# WIFIBT_AP6212.net
KiCad netlist of a schematic drawn in Altium Designer
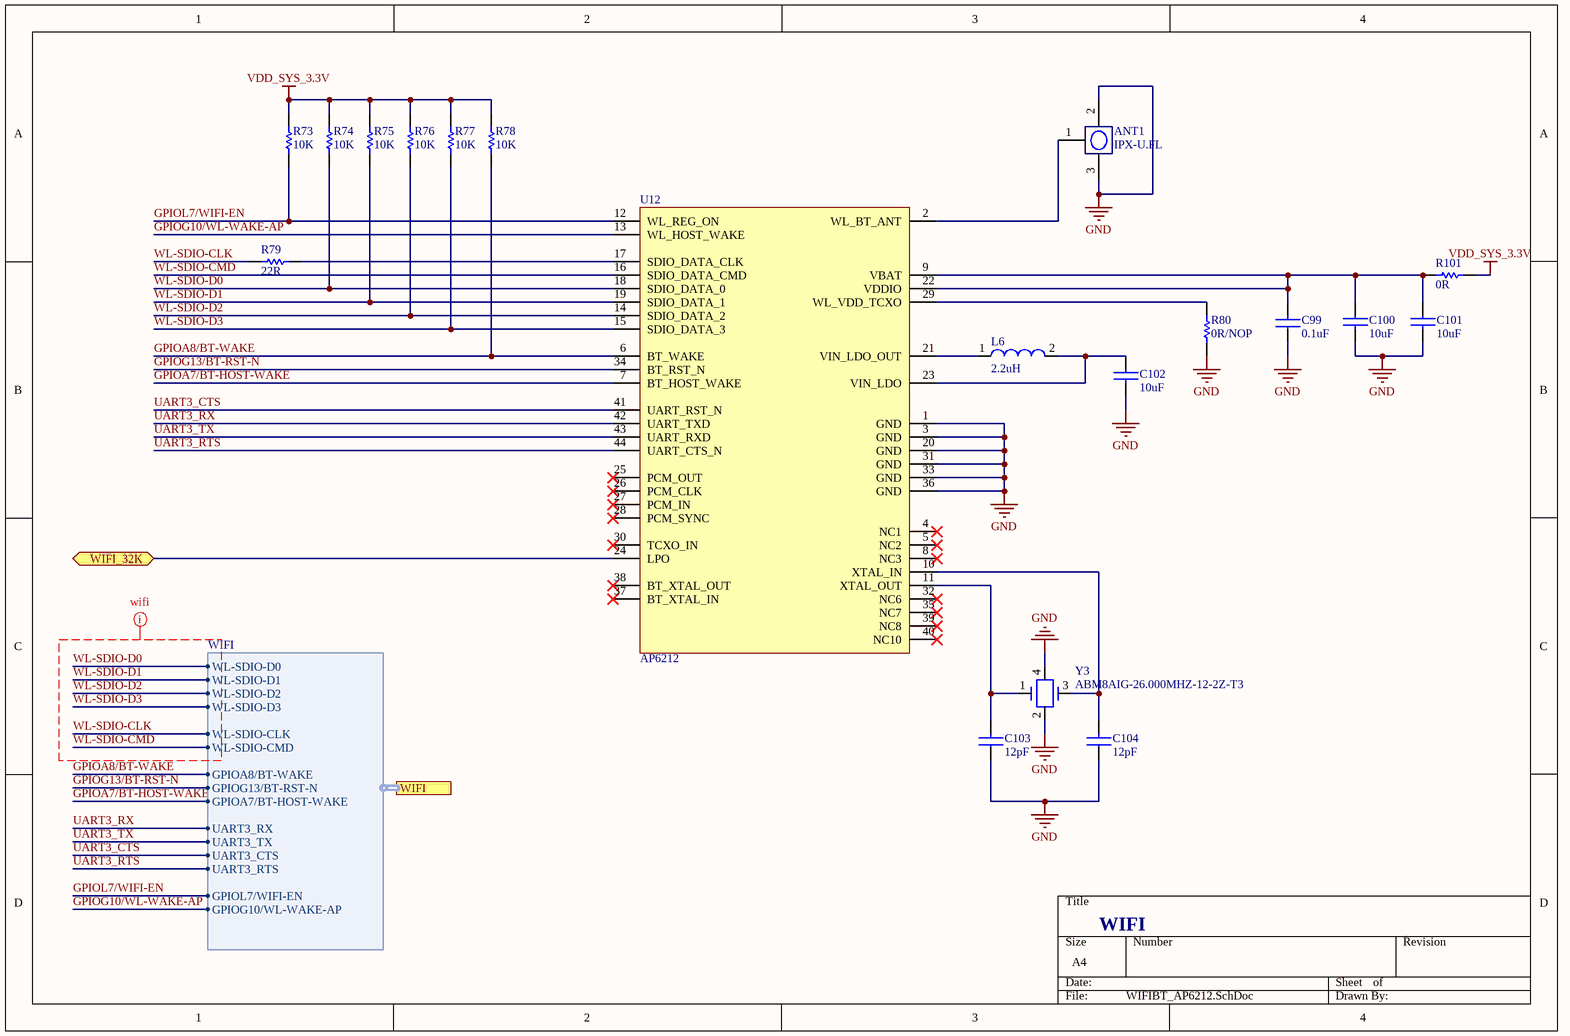
[diagram p0: WIFIBT_AP6212.SchDoc]

(export (version "E")
  (design (tool "Eeschema 10.0.6"))
  (components
    (comp (ref "ANT1") (value "IPX-U.FL") (footprint "UFL") (libsource (lib "MH") (part "ANT1")))
    (comp (ref "C99")
      (value "0.1uF")
      (footprint "C0402")
      (fields (field (name "PART NUMBER") "GCM188L81H104KA57D"))
      (libsource (lib "MH") (part "CAPC"))
    )
    (comp (ref "C100")
      (value "10uF")
      (footprint "C0603")
      (fields (field (name "PART NUMBER") "GRM188R60J106ME47D"))
      (libsource (lib "MH") (part "CAPC"))
    )
    (comp (ref "C101")
      (value "10uF")
      (footprint "C0603")
      (fields (field (name "PART NUMBER") "GRM188R60J106ME47D"))
      (libsource (lib "MH") (part "CAPC"))
    )
    (comp (ref "C102")
      (value "10uF")
      (footprint "C0603")
      (fields (field (name "PART NUMBER") "GRM188R60J106ME47D"))
      (libsource (lib "MH") (part "CAPC"))
    )
    (comp (ref "C103")
      (value "12pF")
      (footprint "C0402")
      (fields (field (name "PART NUMBER") "GRM1555C1H120FA01D"))
      (libsource (lib "MH") (part "CAPC"))
    )
    (comp (ref "C104")
      (value "12pF")
      (footprint "C0402")
      (fields (field (name "PART NUMBER") "GRM1555C1H120FA01D"))
      (libsource (lib "MH") (part "CAPC"))
    )
    (comp (ref "L6")
      (value "2.2uH")
      (footprint "L1008")
      (description "L")
      (fields (field (name "PART NUMBER") "DFE252010-2R2M"))
      (libsource (lib "MH") (part "SELF"))
    )
    (comp (ref "R73")
      (value "10K")
      (footprint "R0402")
      (description "Resistor")
      (fields
        (field (name "PART NUMBER") "CRCW060310K0FKTA")
        (field (name "Comment") "10K,1%")
        (field (name "PUBLISHER") "Altium Limited")
      )
      (libsource (lib "Miscellaneous Devices") (part "Res1"))
    )
    (comp (ref "R74")
      (value "10K")
      (footprint "R0402")
      (description "Resistor")
      (fields
        (field (name "PART NUMBER") "CRCW060310K0FKTA")
        (field (name "Comment") "10K,1%")
        (field (name "PUBLISHER") "Altium Limited")
      )
      (libsource (lib "Miscellaneous Devices") (part "Res1"))
    )
    (comp (ref "R75")
      (value "10K")
      (footprint "R0402")
      (description "Resistor")
      (fields
        (field (name "PART NUMBER") "CRCW060310K0FKTA")
        (field (name "Comment") "10K,1%")
        (field (name "PUBLISHER") "Altium Limited")
      )
      (libsource (lib "Miscellaneous Devices") (part "Res1"))
    )
    (comp (ref "R76")
      (value "10K")
      (footprint "R0402")
      (description "Resistor")
      (fields
        (field (name "PART NUMBER") "CRCW060310K0FKTA")
        (field (name "Comment") "10K,1%")
        (field (name "PUBLISHER") "Altium Limited")
      )
      (libsource (lib "Miscellaneous Devices") (part "Res1"))
    )
    (comp (ref "R77")
      (value "10K")
      (footprint "R0402")
      (description "Resistor")
      (fields
        (field (name "PART NUMBER") "CRCW060310K0FKTA")
        (field (name "Comment") "10K,1%")
        (field (name "PUBLISHER") "Altium Limited")
      )
      (libsource (lib "Miscellaneous Devices") (part "Res1"))
    )
    (comp (ref "R78")
      (value "10K")
      (footprint "R0402")
      (description "Resistor")
      (fields
        (field (name "PART NUMBER") "CRCW060310K0FKTA")
        (field (name "Comment") "10K,1%")
        (field (name "PUBLISHER") "Altium Limited")
      )
      (libsource (lib "Miscellaneous Devices") (part "Res1"))
    )
    (comp (ref "R79")
      (value "22R")
      (footprint "R0402")
      (description "Resistor")
      (fields (field (name "PART NUMBER") "CRCW060322R0FKEA") (field (name "PUBLISHER") "Altium Limited"))
      (libsource (lib "Miscellaneous Devices") (part "Res1"))
    )
    (comp (ref "R80")
      (value "0R/NOP")
      (footprint "R0402")
      (description "Resistor")
      (fields (field (name "PART NUMBER") "ERJ-2GE0R00X") (field (name "PUBLISHER") "Altium Limited"))
      (libsource (lib "Miscellaneous Devices") (part "Res1"))
    )
    (comp (ref "R101")
      (value "0R")
      (footprint "R0402")
      (description "Resistor")
      (fields
        (field (name "PART NUMBER") "ERJ-2GE0R00X")
        (field (name "PART NUMBER_1") "WSL060300000ZEA9")
        (field (name "PUBLISHER") "Altium Limited")
      )
      (libsource (lib "Miscellaneous Devices") (part "Res1"))
    )
    (comp (ref "U12")
      (value "AP6212")
      (footprint "AP6212_44_12X12")
      (description "WiFi Module")
      (libsource (lib "CPU") (part "AP6212"))
    )
    (comp (ref "Y3")
      (value "ABM8AIG-26.000MHZ-12-2Z-T3")
      (footprint "XTL_4_3225")
      (description "32.768KHz MC-306")
      (libsource (lib "MH") (part "CRYS-4P"))
    )
  )
  (nets
    (net (code "2") (name "/GPIOA7{slash}BT-HOST-WAKE") (class "Default")
      (node (ref "U12") (pin "7") (pinfunction "BT_HOST_WAKE_7") (pintype "tri_state"))
    )
    (net (code "3") (name "/GPIOA8{slash}BT-WAKE") (class "Default")
      (node (ref "R78") (pin "1") (pinfunction "1_1") (pintype "passive"))
      (node (ref "U12") (pin "6") (pinfunction "BT_WAKE_6") (pintype "tri_state"))
    )
    (net (code "4") (name "/GPIOG10{slash}WL-WAKE-AP") (class "Default")
      (node (ref "U12") (pin "13") (pinfunction "WL_HOST_WAKE_13") (pintype "tri_state"))
    )
    (net (code "5") (name "/GPIOG13{slash}BT-RST-N") (class "Default")
      (node (ref "U12") (pin "34") (pinfunction "BT_RST_N_34") (pintype "tri_state"))
    )
    (net (code "6") (name "/GPIOL7{slash}WIFI-EN") (class "Default")
      (node (ref "R73") (pin "1") (pinfunction "1_1") (pintype "passive"))
      (node (ref "U12") (pin "12") (pinfunction "WL_REG_ON_12") (pintype "tri_state"))
    )
    (net (code "7") (name "/UART3_CTS") (class "Default")
      (node (ref "U12") (pin "41") (pinfunction "UART_RST_N_41") (pintype "tri_state"))
    )
    (net (code "8") (name "/UART3_RTS") (class "Default")
      (node (ref "U12") (pin "44") (pinfunction "UART_CTS_N_44") (pintype "tri_state"))
    )
    (net (code "9") (name "/UART3_RX") (class "Default")
      (node (ref "U12") (pin "42") (pinfunction "UART_TXD_42") (pintype "tri_state"))
    )
    (net (code "10") (name "/UART3_TX") (class "Default")
      (node (ref "U12") (pin "43") (pinfunction "UART_RXD_43") (pintype "tri_state"))
    )
    (net (code "11") (name "/WIFI_32K") (class "Default")
      (node (ref "U12") (pin "24") (pinfunction "LPO_24") (pintype "tri_state"))
    )
    (net (code "12") (name "/WL-SDIO-CLK") (class "Default")
      (node (ref "R79") (pin "2") (pinfunction "2_2") (pintype "passive"))
    )
    (net (code "13") (name "/WL-SDIO-CMD") (class "Default")
      (node (ref "U12") (pin "16") (pinfunction "SDIO_DATA_CMD_16") (pintype "tri_state"))
    )
    (net (code "14") (name "/WL-SDIO-D0") (class "Default")
      (node (ref "R74") (pin "1") (pinfunction "1_1") (pintype "passive"))
      (node (ref "U12") (pin "18") (pinfunction "SDIO_DATA_0_18") (pintype "tri_state"))
    )
    (net (code "15") (name "/WL-SDIO-D1") (class "Default")
      (node (ref "R75") (pin "1") (pinfunction "1_1") (pintype "passive"))
      (node (ref "U12") (pin "19") (pinfunction "SDIO_DATA_1_19") (pintype "tri_state"))
    )
    (net (code "16") (name "/WL-SDIO-D2") (class "Default")
      (node (ref "R76") (pin "1") (pinfunction "1_1") (pintype "passive"))
      (node (ref "U12") (pin "14") (pinfunction "SDIO_DATA_2_14") (pintype "tri_state"))
    )
    (net (code "17") (name "/WL-SDIO-D3") (class "Default")
      (node (ref "R77") (pin "1") (pinfunction "1_1") (pintype "passive"))
      (node (ref "U12") (pin "15") (pinfunction "SDIO_DATA_3_15") (pintype "tri_state"))
    )
    (net (code "19") (name "GND") (class "Default")
      (node (ref "ANT1") (pin "2") (pinfunction "2_2") (pintype "tri_state"))
      (node (ref "ANT1") (pin "3") (pinfunction "3_3") (pintype "tri_state"))
      (node (ref "C100") (pin "2") (pinfunction "2_2") (pintype "passive"))
      (node (ref "C101") (pin "2") (pinfunction "2_2") (pintype "passive"))
      (node (ref "C102") (pin "2") (pinfunction "2_2") (pintype "passive"))
      (node (ref "C103") (pin "1") (pinfunction "1_1") (pintype "passive"))
      (node (ref "C104") (pin "1") (pinfunction "1_1") (pintype "passive"))
      (node (ref "C99") (pin "1") (pinfunction "1_1") (pintype "passive"))
      (node (ref "R80") (pin "1") (pinfunction "1_1") (pintype "passive"))
      (node (ref "U12") (pin "1") (pinfunction "GND_1") (pintype "tri_state"))
      (node (ref "U12") (pin "20") (pinfunction "GND_20") (pintype "tri_state"))
      (node (ref "U12") (pin "3") (pinfunction "GND_3") (pintype "tri_state"))
      (node (ref "U12") (pin "31") (pinfunction "GND_31") (pintype "tri_state"))
      (node (ref "U12") (pin "33") (pinfunction "GND_33") (pintype "tri_state"))
      (node (ref "U12") (pin "36") (pinfunction "GND_36") (pintype "tri_state"))
      (node (ref "Y3") (pin "2") (pinfunction "2_2") (pintype "passive"))
      (node (ref "Y3") (pin "4") (pinfunction "4_4") (pintype "passive"))
    )
    (net (code "20") (name "Net-(U12-SDIO_DATA_CLK)") (class "Default")
      (node (ref "R79") (pin "1") (pinfunction "1_1") (pintype "passive"))
      (node (ref "U12") (pin "17") (pinfunction "SDIO_DATA_CLK_17") (pintype "tri_state"))
    )
    (net (code "21") (name "Net-(U12-VBAT)") (class "Default")
      (node (ref "C100") (pin "1") (pinfunction "1_1") (pintype "passive"))
      (node (ref "C101") (pin "1") (pinfunction "1_1") (pintype "passive"))
      (node (ref "C99") (pin "2") (pinfunction "2_2") (pintype "passive"))
      (node (ref "R101") (pin "2") (pinfunction "2_2") (pintype "passive"))
      (node (ref "U12") (pin "22") (pinfunction "VDDIO_22") (pintype "tri_state"))
      (node (ref "U12") (pin "9") (pinfunction "VBAT_9") (pintype "tri_state"))
    )
    (net (code "22") (name "Net-(U12-VIN_LDO)") (class "Default")
      (node (ref "C102") (pin "1") (pinfunction "1_1") (pintype "passive"))
      (node (ref "L6") (pin "2") (pinfunction "2_2") (pintype "passive"))
      (node (ref "U12") (pin "23") (pinfunction "VIN_LDO_23") (pintype "tri_state"))
    )
    (net (code "23") (name "Net-(U12-VIN_LDO_OUT)") (class "Default")
      (node (ref "L6") (pin "1") (pinfunction "1_1") (pintype "passive"))
      (node (ref "U12") (pin "21") (pinfunction "VIN_LDO_OUT_21") (pintype "tri_state"))
    )
    (net (code "24") (name "Net-(U12-WL_BT_ANT)") (class "Default")
      (node (ref "ANT1") (pin "1") (pinfunction "1_1") (pintype "tri_state"))
      (node (ref "U12") (pin "2") (pinfunction "WL_BT_ANT_2") (pintype "tri_state"))
    )
    (net (code "25") (name "Net-(U12-WL_VDD_TCXO)") (class "Default")
      (node (ref "R80") (pin "2") (pinfunction "2_2") (pintype "passive"))
      (node (ref "U12") (pin "29") (pinfunction "WL_VDD_TCXO_29") (pintype "tri_state"))
    )
    (net (code "26") (name "Net-(U12-XTAL_IN)") (class "Default")
      (node (ref "C104") (pin "2") (pinfunction "2_2") (pintype "passive"))
      (node (ref "U12") (pin "10") (pinfunction "XTAL_IN_10") (pintype "tri_state"))
      (node (ref "Y3") (pin "3") (pinfunction "3_3") (pintype "passive"))
    )
    (net (code "27") (name "Net-(U12-XTAL_OUT)") (class "Default")
      (node (ref "C103") (pin "2") (pinfunction "2_2") (pintype "passive"))
      (node (ref "U12") (pin "11") (pinfunction "XTAL_OUT_11") (pintype "tri_state"))
      (node (ref "Y3") (pin "1") (pinfunction "1_1") (pintype "passive"))
    )
    (net (code "28") (name "VDD_SYS_3.3V") (class "Default")
      (node (ref "R101") (pin "1") (pinfunction "1_1") (pintype "passive"))
      (node (ref "R73") (pin "2") (pinfunction "2_2") (pintype "passive"))
      (node (ref "R74") (pin "2") (pinfunction "2_2") (pintype "passive"))
      (node (ref "R75") (pin "2") (pinfunction "2_2") (pintype "passive"))
      (node (ref "R76") (pin "2") (pinfunction "2_2") (pintype "passive"))
      (node (ref "R77") (pin "2") (pinfunction "2_2") (pintype "passive"))
      (node (ref "R78") (pin "2") (pinfunction "2_2") (pintype "passive"))
    )
    (net (code "29") (name "unconnected-(U12-BT_XTAL_IN-Pad37)") (class "Default")
      (node (ref "U12") (pin "37") (pinfunction "BT_XTAL_IN_37") (pintype "tri_state+no_connect"))
    )
    (net (code "30") (name "unconnected-(U12-BT_XTAL_OUT-Pad38)") (class "Default")
      (node (ref "U12") (pin "38") (pinfunction "BT_XTAL_OUT_38") (pintype "tri_state+no_connect"))
    )
    (net (code "31") (name "unconnected-(U12-NC1-Pad4)") (class "Default")
      (node (ref "U12") (pin "4") (pinfunction "NC1_4") (pintype "tri_state+no_connect"))
    )
    (net (code "32") (name "unconnected-(U12-NC2-Pad5)") (class "Default")
      (node (ref "U12") (pin "5") (pinfunction "NC2_5") (pintype "tri_state+no_connect"))
    )
    (net (code "33") (name "unconnected-(U12-NC3-Pad8)") (class "Default")
      (node (ref "U12") (pin "8") (pinfunction "NC3_8") (pintype "tri_state+no_connect"))
    )
    (net (code "34") (name "unconnected-(U12-NC6-Pad32)") (class "Default")
      (node (ref "U12") (pin "32") (pinfunction "NC6_32") (pintype "tri_state+no_connect"))
    )
    (net (code "35") (name "unconnected-(U12-NC7-Pad35)") (class "Default")
      (node (ref "U12") (pin "35") (pinfunction "NC7_35") (pintype "tri_state+no_connect"))
    )
    (net (code "36") (name "unconnected-(U12-NC8-Pad39)") (class "Default")
      (node (ref "U12") (pin "39") (pinfunction "NC8_39") (pintype "tri_state+no_connect"))
    )
    (net (code "37") (name "unconnected-(U12-NC10-Pad40)") (class "Default")
      (node (ref "U12") (pin "40") (pinfunction "NC10_40") (pintype "tri_state+no_connect"))
    )
    (net (code "38") (name "unconnected-(U12-PCM_CLK-Pad26)") (class "Default")
      (node (ref "U12") (pin "26") (pinfunction "PCM_CLK_26") (pintype "tri_state+no_connect"))
    )
    (net (code "39") (name "unconnected-(U12-PCM_IN-Pad27)") (class "Default")
      (node (ref "U12") (pin "27") (pinfunction "PCM_IN_27") (pintype "tri_state+no_connect"))
    )
    (net (code "40") (name "unconnected-(U12-PCM_OUT-Pad25)") (class "Default")
      (node (ref "U12") (pin "25") (pinfunction "PCM_OUT_25") (pintype "tri_state+no_connect"))
    )
    (net (code "41") (name "unconnected-(U12-PCM_SYNC-Pad28)") (class "Default")
      (node (ref "U12") (pin "28") (pinfunction "PCM_SYNC_28") (pintype "tri_state+no_connect"))
    )
    (net (code "42") (name "unconnected-(U12-TCXO_IN-Pad30)") (class "Default")
      (node (ref "U12") (pin "30") (pinfunction "TCXO_IN_30") (pintype "tri_state+no_connect"))
    )
  )
)
